# VenusGPS.net
KiCad netlist of a schematic drawn in EAGLE
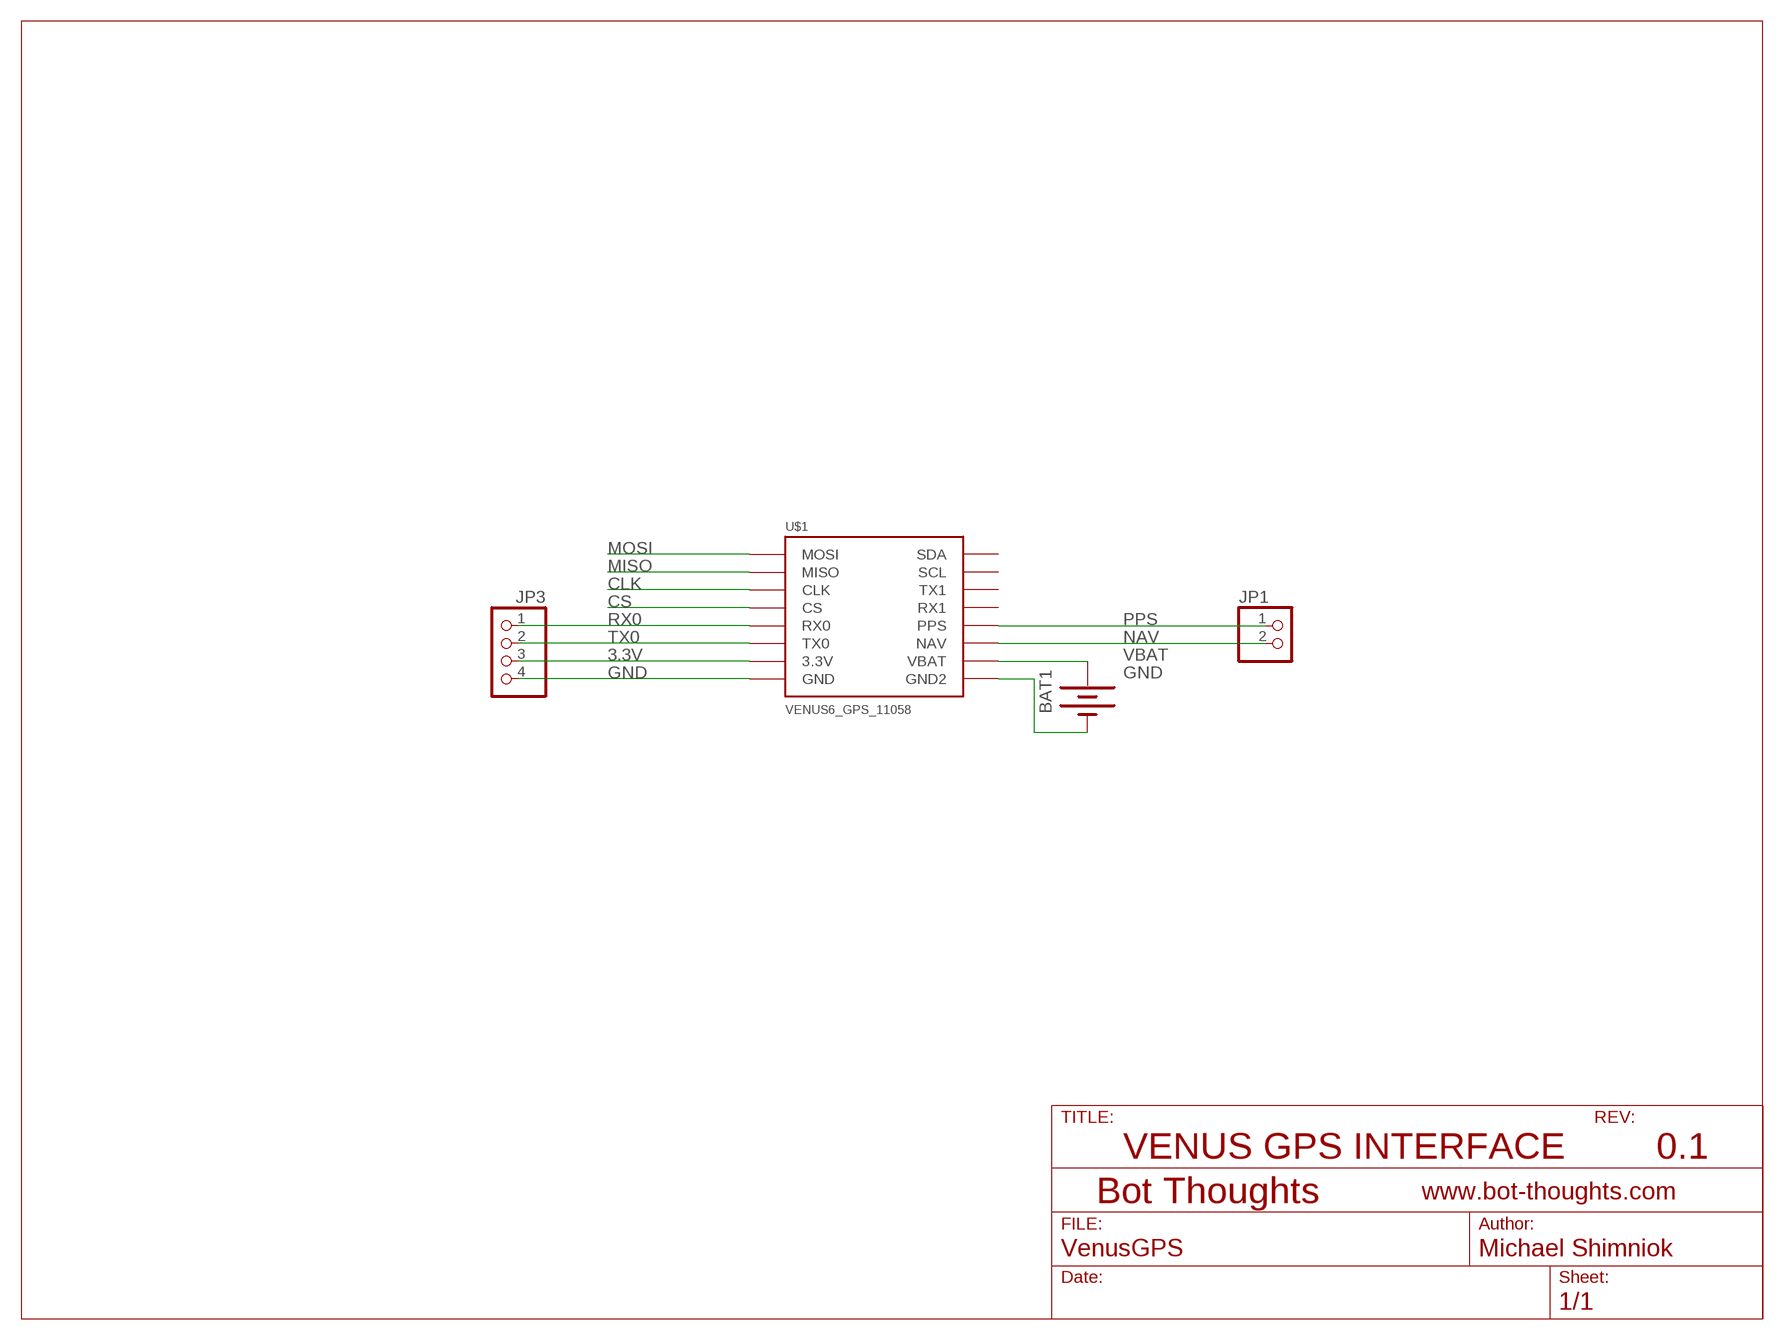
[diagram p0: schematic, sheet 1]

(export (version "E")
  (design (tool "Eeschema 10.0.6"))
  (components
    (comp (ref "BAT1")
      (value "BATTERY12MM")
      (footprint "eagle-import:BATTCON_12MM")
      (fields (field (name "PARTNO") "3000"))
      (libsource (lib "eagle-import") (part "BATTERY12MM"))
    )
    (comp (ref "JP1")
      (value "PINHD-1X02_2.54")
      (footprint "eagle-import:1X02")
      (libsource (lib "eagle-import") (part "PINHD-1X02_2.54"))
    )
    (comp (ref "JP3")
      (value "PINHD-1X04_2.54")
      (footprint "eagle-import:1X04")
      (libsource (lib "eagle-import") (part "PINHD-1X04_2.54"))
    )
    (comp (ref "U$1")
      (value "VENUS6_GPS_11058")
      (footprint "eagle-import:VENUS6")
      (libsource (lib "eagle-import") (part "VENUS6_GPS_11058"))
    )
  )
  (nets
    (net (code "1") (name "/3.3V") (class "Default")
      (node (ref "JP3") (pin "3") (pinfunction "3_3") (pintype "passive"))
      (node (ref "U$1") (pin "P7") (pinfunction "3.3V_P7") (pintype "bidirectional"))
    )
    (net (code "2") (name "/CLK") (class "Default")
      (node (ref "U$1") (pin "P3") (pinfunction "CLK_P3") (pintype "bidirectional"))
    )
    (net (code "3") (name "/CS") (class "Default")
      (node (ref "U$1") (pin "P4") (pinfunction "CS_P4") (pintype "bidirectional"))
    )
    (net (code "4") (name "/GND") (class "Default")
      (node (ref "BAT1") (pin "GND") (pinfunction "-_GND") (pintype "power_in"))
      (node (ref "JP3") (pin "4") (pinfunction "4_4") (pintype "passive"))
      (node (ref "U$1") (pin "P8") (pinfunction "GND_P8") (pintype "bidirectional"))
      (node (ref "U$1") (pin "P9") (pinfunction "GND2_P9") (pintype "bidirectional"))
    )
    (net (code "5") (name "/MISO") (class "Default")
      (node (ref "U$1") (pin "P2") (pinfunction "MISO_P2") (pintype "bidirectional"))
    )
    (net (code "6") (name "/MOSI") (class "Default")
      (node (ref "U$1") (pin "P1") (pinfunction "MOSI_P1") (pintype "bidirectional"))
    )
    (net (code "7") (name "/NAV") (class "Default")
      (node (ref "JP1") (pin "2") (pinfunction "2_2") (pintype "passive"))
      (node (ref "U$1") (pin "P11") (pinfunction "NAV_P11") (pintype "bidirectional"))
    )
    (net (code "8") (name "/PPS") (class "Default")
      (node (ref "JP1") (pin "1") (pinfunction "1_1") (pintype "passive"))
      (node (ref "U$1") (pin "P12") (pinfunction "PPS_P12") (pintype "bidirectional"))
    )
    (net (code "9") (name "/RX0") (class "Default")
      (node (ref "JP3") (pin "1") (pinfunction "1_1") (pintype "passive"))
      (node (ref "U$1") (pin "P5") (pinfunction "RX0_P5") (pintype "bidirectional"))
    )
    (net (code "10") (name "/TX0") (class "Default")
      (node (ref "JP3") (pin "2") (pinfunction "2_2") (pintype "passive"))
      (node (ref "U$1") (pin "P6") (pinfunction "TX0_P6") (pintype "bidirectional"))
    )
    (net (code "11") (name "/VBAT") (class "Default")
      (node (ref "BAT1") (pin "PWR@1") (pinfunction "+_PWR@1") (pintype "power_in"))
      (node (ref "U$1") (pin "P10") (pinfunction "VBAT_P10") (pintype "bidirectional"))
    )
    (net (code "12") (name "unconnected-(U$1-RX1-PadP13)") (class "Default")
      (node (ref "U$1") (pin "P13") (pinfunction "RX1_P13") (pintype "bidirectional"))
    )
    (net (code "13") (name "unconnected-(U$1-SCL-PadP15)") (class "Default")
      (node (ref "U$1") (pin "P15") (pinfunction "SCL_P15") (pintype "bidirectional"))
    )
    (net (code "14") (name "unconnected-(U$1-SDA-PadP16)") (class "Default")
      (node (ref "U$1") (pin "P16") (pinfunction "SDA_P16") (pintype "bidirectional"))
    )
    (net (code "15") (name "unconnected-(U$1-TX1-PadP14)") (class "Default")
      (node (ref "U$1") (pin "P14") (pinfunction "TX1_P14") (pintype "bidirectional"))
    )
  )
)
